# AS5048B_Breakout.net
KiCad netlist of a schematic drawn in Altium Designer
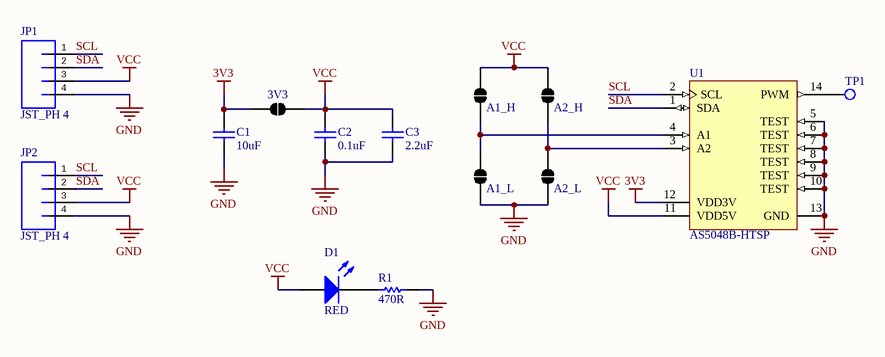
[diagram p0: AS5048B_Breakout.SchDoc]

(export (version "E")
  (design (tool "Eeschema 10.0.6"))
  (components
    (comp (ref "3V3")
      (value "Solder Jumper")
      (footprint "SOLDER JUMPER")
      (libsource (lib "Components") (part "Solder Jumper"))
    )
    (comp (ref "A1_H")
      (value "A1_H")
      (footprint "SOLDER JUMPER")
      (libsource (lib "Components") (part "Solder Jumper"))
    )
    (comp (ref "A1_L")
      (value "A1_L")
      (footprint "SOLDER JUMPER")
      (libsource (lib "Components") (part "Solder Jumper"))
    )
    (comp (ref "A2_H")
      (value "A2_H")
      (footprint "SOLDER JUMPER")
      (libsource (lib "Components") (part "Solder Jumper"))
    )
    (comp (ref "A2_L")
      (value "A2_L")
      (footprint "SOLDER JUMPER")
      (libsource (lib "Components") (part "Solder Jumper"))
    )
    (comp (ref "C1")
      (value "10uF")
      (footprint "CAPC0603(1608)100_L")
      (description "CAP 10uF 6.3V ±10% 0603 (1608 Metric) Thickness 1mm SMD")
      (fields (field (name "TOLERANCE") "Â±10%"))
      (libsource (lib "Altium Content Vault") (part "CMP-1035-02796-1"))
    )
    (comp (ref "C2")
      (value "0.1uF")
      (footprint "CAPC0603(1608)100_L")
      (description "CAP 100nF 50V ±5% 0603 (1608 Metric) Thickness 1mm SMD")
      (fields (field (name "TOLERANCE") "Â±5%"))
      (libsource (lib "Altium Content Vault") (part "CMP-1035-02591-1"))
    )
    (comp (ref "C3")
      (value "2.2uF")
      (footprint "CAPC0603(1608)100_L")
      (description "CAP 2.2uF 25V ±10% 0603 (1608 Metric) Thickness 1mm SMD")
      (fields (field (name "TOLERANCE") "Â±10%"))
      (libsource (lib "Altium Content Vault") (part "CMP-1035-02767-1"))
    )
    (comp (ref "D1")
      (value "RED")
      (footprint "0603_A")
      (description "SMD mono-color Chip LED, WL-SMCW, Red")
      (fields (field (name "MANUFACTURER") "Wuerth Elektronik") (field (name "PARTNUMBER") "150060RS75000"))
      (libsource (lib "Altium Content Vault") (part "CMP-1426-00001-1"))
    )
    (comp (ref "JP1")
      (value "JST_PH 4")
      (footprint "JST-4-PTH-RIGHT-ANGLE")
      (libsource (lib "Components") (part "JST_PH 4"))
    )
    (comp (ref "JP2")
      (value "JST_PH 4")
      (footprint "JST-4-PTH-RIGHT-ANGLE")
      (libsource (lib "Components") (part "JST_PH 4"))
    )
    (comp (ref "R1")
      (value "470R")
      (footprint "RESC0603(1608)_L")
      (description "470R 0.1W 5% 0603 (1608 Metric)  SMD")
      (fields (field (name "TOLERANCE") "5 %") (field (name "POWER") "0.1 W"))
      (libsource (lib "Altium Content Vault") (part "CMP-1012-00066-1"))
    )
    (comp (ref "TP1")
      (value "Test Point")
      (footprint "TEST POINT")
      (libsource (lib "Components") (part "Test Point"))
    )
    (comp (ref "U1")
      (value "AS5048B-HTSP")
      (footprint "AMS-TSSOP-14-5000X4400DE_L")
      (description "Magnetic Rotary Encoder 14-bit Angular Position Sensor, 3.3 or 5 V, TSSOP-14, Pb-Free, Reel")
      (fields (field (name "MANUFACTURER") "AMS"))
      (libsource (lib "Altium Content Vault") (part "AMS-AS5048B-TSSOP-14"))
    )
  )
  (nets
    (net (code "1") (name "/SCL") (class "Default")
      (node (ref "JP1") (pin "1") (pinfunction "1_1") (pintype "passive"))
      (node (ref "JP2") (pin "1") (pinfunction "1_1") (pintype "passive"))
      (node (ref "U1") (pin "2") (pinfunction "SCL_2") (pintype "input"))
    )
    (net (code "2") (name "/SDA") (class "Default")
      (node (ref "JP1") (pin "2") (pinfunction "2_2") (pintype "passive"))
      (node (ref "JP2") (pin "2") (pinfunction "2_2") (pintype "passive"))
      (node (ref "U1") (pin "1") (pinfunction "SDA_1") (pintype "bidirectional"))
    )
    (net (code "3") (name "3V3") (class "Default")
      (node (ref "3V3") (pin "2") (pinfunction "2_2") (pintype "passive"))
      (node (ref "C1") (pin "1") (pinfunction "1_1") (pintype "passive"))
      (node (ref "U1") (pin "12") (pinfunction "VDD3V_12") (pintype "power_in"))
    )
    (net (code "4") (name "GND") (class "Default")
      (node (ref "A1_L") (pin "1") (pinfunction "1_1") (pintype "passive"))
      (node (ref "A2_L") (pin "1") (pinfunction "1_1") (pintype "passive"))
      (node (ref "C1") (pin "2") (pinfunction "2_2") (pintype "passive"))
      (node (ref "C2") (pin "1") (pinfunction "1_1") (pintype "passive"))
      (node (ref "C3") (pin "1") (pinfunction "1_1") (pintype "passive"))
      (node (ref "JP1") (pin "4") (pinfunction "4_4") (pintype "passive"))
      (node (ref "JP2") (pin "4") (pinfunction "4_4") (pintype "passive"))
      (node (ref "R1") (pin "1") (pinfunction "1_1") (pintype "passive"))
      (node (ref "U1") (pin "10") (pinfunction "TEST_10") (pintype "input"))
      (node (ref "U1") (pin "13") (pinfunction "GND_13") (pintype "power_in"))
      (node (ref "U1") (pin "5") (pinfunction "TEST_5") (pintype "input"))
      (node (ref "U1") (pin "6") (pinfunction "TEST_6") (pintype "input"))
      (node (ref "U1") (pin "7") (pinfunction "TEST_7") (pintype "input"))
      (node (ref "U1") (pin "8") (pinfunction "TEST_8") (pintype "input"))
      (node (ref "U1") (pin "9") (pinfunction "TEST_9") (pintype "input"))
    )
    (net (code "5") (name "Net-(D1-K)") (class "Default")
      (node (ref "D1") (pin "1") (pinfunction "K_1") (pintype "passive"))
      (node (ref "R1") (pin "2") (pinfunction "2_2") (pintype "passive"))
    )
    (net (code "6") (name "Net-(U1-A1)") (class "Default")
      (node (ref "A1_H") (pin "1") (pinfunction "1_1") (pintype "passive"))
      (node (ref "A1_L") (pin "2") (pinfunction "2_2") (pintype "passive"))
      (node (ref "U1") (pin "4") (pinfunction "A1_4") (pintype "input"))
    )
    (net (code "7") (name "Net-(U1-A2)") (class "Default")
      (node (ref "A2_H") (pin "1") (pinfunction "1_1") (pintype "passive"))
      (node (ref "A2_L") (pin "2") (pinfunction "2_2") (pintype "passive"))
      (node (ref "U1") (pin "3") (pinfunction "A2_3") (pintype "input"))
    )
    (net (code "8") (name "Net-(U1-PWM)") (class "Default")
      (node (ref "TP1") (pin "1") (pinfunction "1_1") (pintype "passive"))
      (node (ref "U1") (pin "14") (pinfunction "PWM_14") (pintype "output"))
    )
    (net (code "9") (name "VCC") (class "Default")
      (node (ref "3V3") (pin "1") (pinfunction "1_1") (pintype "passive"))
      (node (ref "A1_H") (pin "2") (pinfunction "2_2") (pintype "passive"))
      (node (ref "A2_H") (pin "2") (pinfunction "2_2") (pintype "passive"))
      (node (ref "C2") (pin "2") (pinfunction "2_2") (pintype "passive"))
      (node (ref "C3") (pin "2") (pinfunction "2_2") (pintype "passive"))
      (node (ref "D1") (pin "2") (pinfunction "A_2") (pintype "passive"))
      (node (ref "JP1") (pin "3") (pinfunction "3_3") (pintype "passive"))
      (node (ref "JP2") (pin "3") (pinfunction "3_3") (pintype "passive"))
      (node (ref "U1") (pin "11") (pinfunction "VDD5V_11") (pintype "power_in"))
    )
  )
)
